# L-D5019-08.net
KiCad netlist of a schematic drawn in Altium Designer
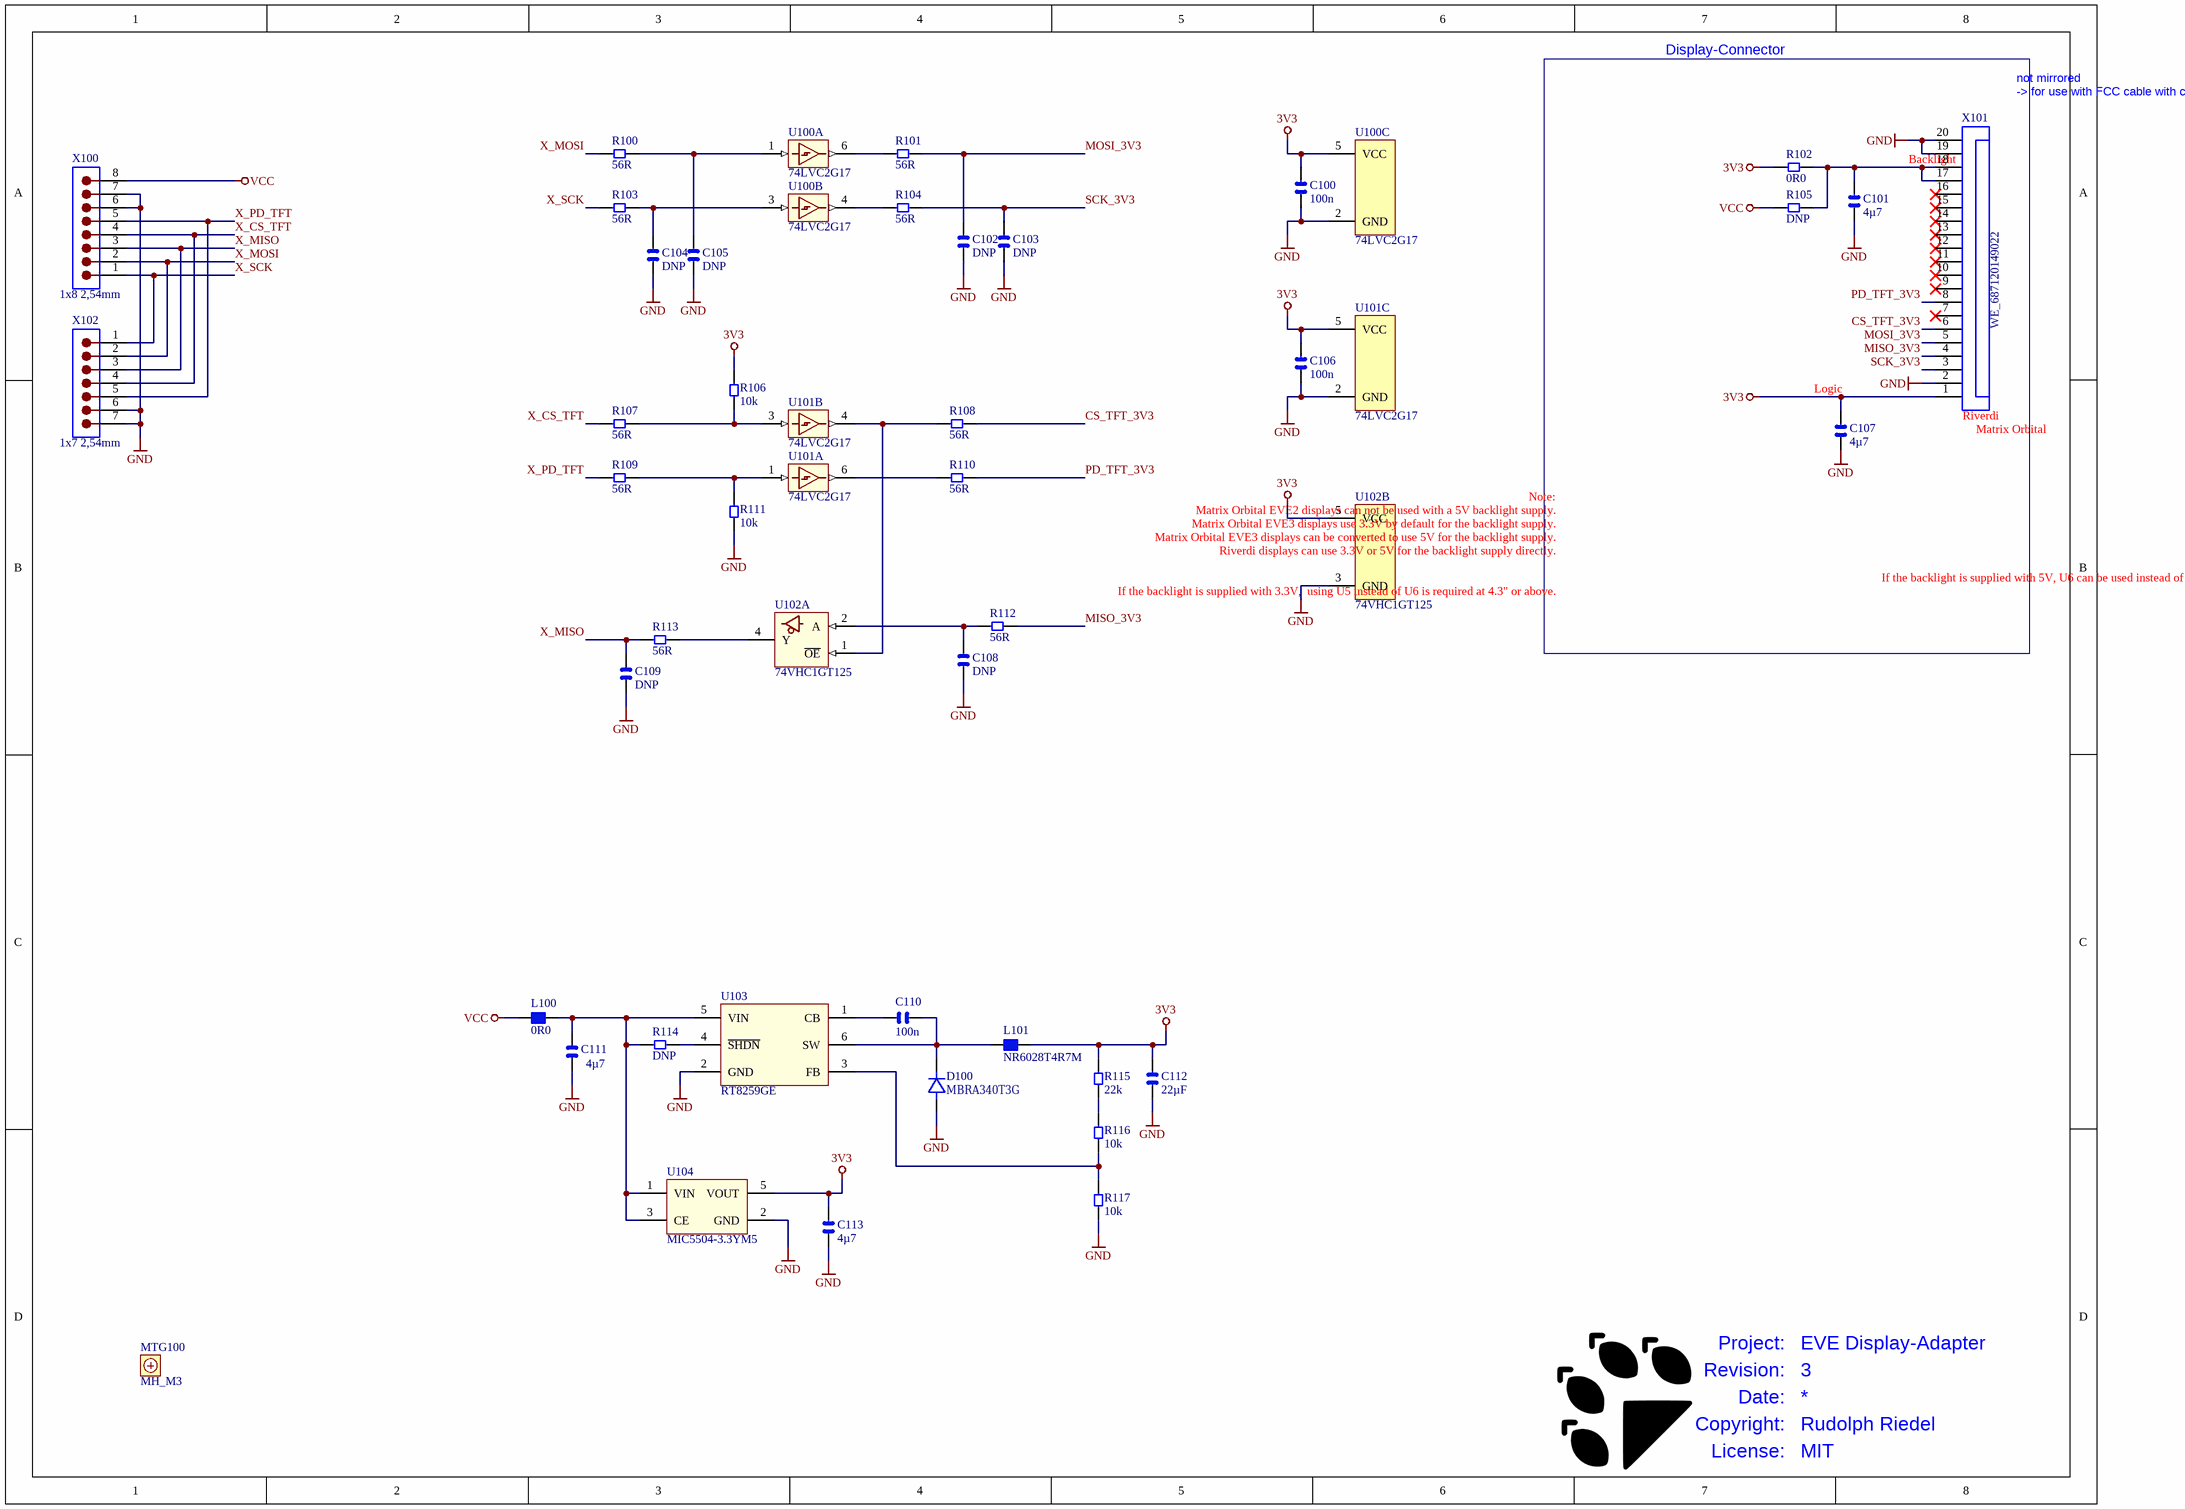
[diagram p0: L-D5019-08.SchDoc]

(export (version "E")
  (design (tool "Eeschema 10.0.6"))
  (components
    (comp (ref "C100")
      (value "100n")
      (footprint "CAPC2012X14L")
      (description "0805 Chip Capacitor")
      (fields (field (name "PART NUMBER") "CAPC_0805") (field (name "EDITOR") "rriedel"))
      (libsource (lib "HW-Labor_GF") (part "CAP_2_V2"))
    )
    (comp (ref "C101")
      (value "4µ7")
      (footprint "CAPC2012X14L")
      (description "0805 Chip Capacitor")
      (fields (field (name "PART NUMBER") "CAPC_0805") (field (name "ERSTELLER") "rriedel"))
      (libsource (lib "HW-Labor_GF") (part "CAP_2_V2"))
    )
    (comp (ref "C102")
      (value "DNP")
      (footprint "CAPC2012X14L")
      (description "0805 Chip Capacitor")
      (fields (field (name "PART NUMBER") "CAPC_0805") (field (name "EDITOR") "rriedel"))
      (libsource (lib "HW-Labor_GF") (part "CAP_2_V2"))
    )
    (comp (ref "C103")
      (value "DNP")
      (footprint "CAPC2012X14L")
      (description "0805 Chip Capacitor")
      (fields (field (name "PART NUMBER") "CAPC_0805") (field (name "EDITOR") "rriedel"))
      (libsource (lib "HW-Labor_GF") (part "CAP_2_V2"))
    )
    (comp (ref "C104")
      (value "DNP")
      (footprint "CAPC2012X14L")
      (description "0805 Chip Capacitor")
      (fields (field (name "PART NUMBER") "CAPC_0805") (field (name "EDITOR") "rriedel"))
      (libsource (lib "HW-Labor_GF") (part "CAP_2_V2"))
    )
    (comp (ref "C105")
      (value "DNP")
      (footprint "CAPC2012X14L")
      (description "0805 Chip Capacitor")
      (fields (field (name "PART NUMBER") "CAPC_0805") (field (name "EDITOR") "rriedel"))
      (libsource (lib "HW-Labor_GF") (part "CAP_2_V2"))
    )
    (comp (ref "C106")
      (value "100n")
      (footprint "CAPC2012X14L")
      (description "0805 Chip Capacitor")
      (fields (field (name "PART NUMBER") "CAPC_0805") (field (name "EDITOR") "rriedel"))
      (libsource (lib "HW-Labor_GF") (part "CAP_2_V2"))
    )
    (comp (ref "C107")
      (value "4µ7")
      (footprint "CAPC2012X14L")
      (description "0805 Chip Capacitor")
      (fields (field (name "PART NUMBER") "CAPC_0805") (field (name "ERSTELLER") "rriedel"))
      (libsource (lib "HW-Labor_GF") (part "CAP_2_V2"))
    )
    (comp (ref "C108")
      (value "DNP")
      (footprint "CAPC2012X14L")
      (description "0805 Chip Capacitor")
      (fields (field (name "PART NUMBER") "CAPC_0805") (field (name "EDITOR") "rriedel"))
      (libsource (lib "HW-Labor_GF") (part "CAP_2_V2"))
    )
    (comp (ref "C109")
      (value "DNP")
      (footprint "CAPC2012X14L")
      (description "0805 Chip Capacitor")
      (fields (field (name "PART NUMBER") "CAPC_0805") (field (name "EDITOR") "rriedel"))
      (libsource (lib "HW-Labor_GF") (part "CAP_2_V2"))
    )
    (comp (ref "C110")
      (value "100n")
      (footprint "CAPC2012X14L")
      (description "0805 Chip Capacitor")
      (fields (field (name "PART NUMBER") "CAPC_0805") (field (name "EDITOR") "rriedel"))
      (libsource (lib "HW-Labor_GF") (part "CAP_2_V2"))
    )
    (comp (ref "C111")
      (value "4µ7")
      (footprint "CAPC3216X19N")
      (description "1206 Chip Capacitor")
      (fields (field (name "PART NUMBER") "CAPC_1206") (field (name "EDITOR") "rriedel"))
      (libsource (lib "HW-Labor_GF") (part "CAP_2_V2"))
    )
    (comp (ref "C112")
      (value "22µF")
      (footprint "CAPC3216X19N")
      (description "1206 Chip Capacitor")
      (fields (field (name "PART NUMBER") "CAPC_1206") (field (name "EDITOR") "rriedel"))
      (libsource (lib "HW-Labor_GF") (part "CAP_2_V2"))
    )
    (comp (ref "C113")
      (value "4µ7")
      (footprint "CAPC2012X14L")
      (description "0805 Chip Capacitor")
      (fields (field (name "PART NUMBER") "CAPC_0805") (field (name "ERSTELLER") "rriedel"))
      (libsource (lib "HW-Labor_GF") (part "CAP_2_V2"))
    )
    (comp (ref "D100")
      (value "MBRA340T3G‎")
      (footprint "DIOM5226X23N")
      (description "Schottky Gleichrichterdiode, 40V / 3A / 450mV")
      (fields
        (field (name "MANUFACTURER") "ON Semiconductor")
        (field (name "DISTRIBUTOR_1_PART_NUMBER") "MBRA340T3GOSCT-ND")
        (field (name "EDITOR") "rriedel")
      )
      (libsource (lib "HW-Labor_GF") (part "Diode_A2_K1"))
    )
    (comp (ref "L100")
      (value "0R0")
      (footprint "INDC2012X10L")
      (description "0805 Chip Inductor")
      (fields (field (name "PART NUMBER") "INDC_0805") (field (name "EDITOR") "rriedel"))
      (libsource (lib "HW-Labor_GF") (part "IND_2_V1"))
    )
    (comp (ref "L101")
      (value "NR6028T4R7M")
      (footprint "TaiyoYuden_NR6028")
      (description "4,7µH, shielded, 2,7A, 40mR")
      (fields
        (field (name "MANUFACTURER") "Taiyo Yuden")
        (field (name "DISTRIBUTOR_1_PART_NUMBER") "587-2100-1-ND")
        (field (name "EDITOR") "rriedel")
      )
      (libsource (lib "HW-Labor_GF") (part "IND_2_V1"))
    )
    (comp (ref "MTG100")
      (value "MH_M3")
      (footprint "HOLE_3_2MM")
      (description "Mounting-Hole for M3 screws")
      (fields (field (name "EDITOR") "rriedel"))
      (libsource (lib "HW-Labor_GF") (part "MTG_V1"))
    )
    (comp (ref "R100")
      (value "56R")
      (footprint "RESC2012X06L")
      (description "0805 Chip Resistor")
      (fields (field (name "PART NUMBER") "RESC_0805") (field (name "EDITOR") "rriedel"))
      (libsource (lib "HW-Labor_GF") (part "RES_2_V2"))
    )
    (comp (ref "R101")
      (value "56R")
      (footprint "RESC2012X06L")
      (description "0805 Chip Resistor")
      (fields (field (name "PART NUMBER") "RESC_0805") (field (name "EDITOR") "rriedel"))
      (libsource (lib "HW-Labor_GF") (part "RES_2_V2"))
    )
    (comp (ref "R102")
      (value "0R0")
      (footprint "RESC2012X06L")
      (description "0805 Chip Resistor")
      (fields (field (name "PART NUMBER") "RESC_0805") (field (name "EDITOR") "rriedel"))
      (libsource (lib "HW-Labor_GF") (part "RES_2_V2"))
    )
    (comp (ref "R103")
      (value "56R")
      (footprint "RESC2012X06L")
      (description "0805 Chip Resistor")
      (fields (field (name "PART NUMBER") "RESC_0805") (field (name "EDITOR") "rriedel"))
      (libsource (lib "HW-Labor_GF") (part "RES_2_V2"))
    )
    (comp (ref "R104")
      (value "56R")
      (footprint "RESC2012X06L")
      (description "0805 Chip Resistor")
      (fields (field (name "PART NUMBER") "RESC_0805") (field (name "EDITOR") "rriedel"))
      (libsource (lib "HW-Labor_GF") (part "RES_2_V2"))
    )
    (comp (ref "R105")
      (value "DNP")
      (footprint "RESC2012X06L")
      (description "0805 Chip Resistor")
      (fields (field (name "PART NUMBER") "RESC_0805") (field (name "EDITOR") "rriedel"))
      (libsource (lib "HW-Labor_GF") (part "RES_2_V2"))
    )
    (comp (ref "R106")
      (value "10k")
      (footprint "RESC2012X06L")
      (description "0805 Chip Resistor")
      (fields (field (name "PART NUMBER") "RESC_0805") (field (name "EDITOR") "rriedel"))
      (libsource (lib "HW-Labor_GF") (part "RES_2_V2"))
    )
    (comp (ref "R107")
      (value "56R")
      (footprint "RESC2012X06L")
      (description "0805 Chip Resistor")
      (fields (field (name "PART NUMBER") "RESC_0805") (field (name "EDITOR") "rriedel"))
      (libsource (lib "HW-Labor_GF") (part "RES_2_V2"))
    )
    (comp (ref "R108")
      (value "56R")
      (footprint "RESC2012X06L")
      (description "0805 Chip Resistor")
      (fields (field (name "PART NUMBER") "RESC_0805") (field (name "EDITOR") "rriedel"))
      (libsource (lib "HW-Labor_GF") (part "RES_2_V2"))
    )
    (comp (ref "R109")
      (value "56R")
      (footprint "RESC2012X06L")
      (description "0805 Chip Resistor")
      (fields (field (name "PART NUMBER") "RESC_0805") (field (name "EDITOR") "rriedel"))
      (libsource (lib "HW-Labor_GF") (part "RES_2_V2"))
    )
    (comp (ref "R110")
      (value "56R")
      (footprint "RESC2012X06L")
      (description "0805 Chip Resistor")
      (fields (field (name "PART NUMBER") "RESC_0805") (field (name "EDITOR") "rriedel"))
      (libsource (lib "HW-Labor_GF") (part "RES_2_V2"))
    )
    (comp (ref "R111")
      (value "10k")
      (footprint "RESC2012X06L")
      (description "0805 Chip Resistor")
      (fields (field (name "PART NUMBER") "RESC_0805") (field (name "EDITOR") "rriedel"))
      (libsource (lib "HW-Labor_GF") (part "RES_2_V2"))
    )
    (comp (ref "R112")
      (value "56R")
      (footprint "RESC2012X06L")
      (description "0805 Chip Resistor")
      (fields (field (name "PART NUMBER") "RESC_0805") (field (name "EDITOR") "rriedel"))
      (libsource (lib "HW-Labor_GF") (part "RES_2_V2"))
    )
    (comp (ref "R113")
      (value "56R")
      (footprint "RESC2012X06L")
      (description "0805 Chip Resistor")
      (fields (field (name "PART NUMBER") "RESC_0805") (field (name "EDITOR") "rriedel"))
      (libsource (lib "HW-Labor_GF") (part "RES_2_V2"))
    )
    (comp (ref "R114")
      (value "DNP")
      (footprint "RESC2012X06L")
      (description "0805 Chip Resistor")
      (fields (field (name "PART NUMBER") "RESC_0805") (field (name "EDITOR") "rriedel"))
      (libsource (lib "HW-Labor_GF") (part "RES_2_V2"))
    )
    (comp (ref "R115")
      (value "22k")
      (footprint "RESC2012X06L")
      (description "0805 Chip Resistor")
      (fields (field (name "PART NUMBER") "RESC_0805") (field (name "EDITOR") "rriedel"))
      (libsource (lib "HW-Labor_GF") (part "RES_2_V2"))
    )
    (comp (ref "R116")
      (value "10k")
      (footprint "RESC2012X06L")
      (description "0805 Chip Resistor")
      (fields (field (name "PART NUMBER") "RESC_0805") (field (name "EDITOR") "rriedel"))
      (libsource (lib "HW-Labor_GF") (part "RES_2_V2"))
    )
    (comp (ref "R117")
      (value "10k")
      (footprint "RESC2012X06L")
      (description "0805 Chip Resistor")
      (fields (field (name "PART NUMBER") "RESC_0805") (field (name "EDITOR") "rriedel"))
      (libsource (lib "HW-Labor_GF") (part "RES_2_V2"))
    )
    (comp (ref "U100")
      (value "74LVC2G17")
      (footprint "SOT95P280X110-6N")
      (description "Dual Schmitt-Trigger Buffer with 5.5V tolerant inputs")
      (fields
        (field (name "MANUFACTURER") "TI")
        (field (name "DISTRIBUTOR_1_PART_NUMBER") "296-SN74LVC2G17DBVRCT-ND‎")
        (field (name "EDITOR") "rriedel")
      )
      (libsource (lib "HW-Labor_GF") (part "74LVC2G17"))
    )
    (comp (ref "U101")
      (value "74LVC2G17")
      (footprint "SOT95P280X110-6N")
      (description "Dual Schmitt-Trigger Buffer with 5.5V tolerant inputs")
      (fields
        (field (name "MANUFACTURER") "TI")
        (field (name "DISTRIBUTOR_1_PART_NUMBER") "296-SN74LVC2G17DBVRCT-ND‎")
        (field (name "EDITOR") "rriedel")
      )
      (libsource (lib "HW-Labor_GF") (part "74LVC2G17"))
    )
    (comp (ref "U102")
      (value "74VHC1GT125")
      (footprint "SOT95P280X110-5N")
      (description "1x Buffer with OE; 3-state,Level Shifter 3,3V to 5V and 5V to 3.3V")
      (fields
        (field (name "MANUFACTURER") "ON Semiconductor")
        (field (name "DISTRIBUTOR_1_PART_NUMBER") "1703291")
        (field (name "EDITOR") "rriedel")
      )
      (libsource (lib "HW-Labor_GF") (part "74LVC1G125G"))
    )
    (comp (ref "U103")
      (value "RT8259GE")
      (footprint "SOT95P280X110-6N")
      (description "Step-Down DC/DC Regulator, 24V, 1.2A, 1,4MHz")
      (fields
        (field (name "MANUFACTURER") "Richtek")
        (field (name "DISTRIBUTOR_1_PART_NUMBER") "1028-1497-1-ND")
        (field (name "EDITOR") "rriedel")
      )
      (libsource (lib "HW-Labor_GF") (part "StepDown_SOT23-6"))
    )
    (comp (ref "U104")
      (value "MIC5504-3.3YM5")
      (footprint "SOT95P280X110-5N")
      (description "300 mA LDO,  Vin=2,5V…5,5V, Vout= 3,3V, -40°C..125°C")
      (fields
        (field (name "MANUFACTURER") "Microchip")
        (field (name "DISTRIBUTOR_1_PART_NUMBER") "2510377")
        (field (name "EDITOR") "rriedel")
      )
      (libsource (lib "HW-Labor_GF") (part "LDO_SOT23-5"))
    )
    (comp (ref "X100")
      (value "1x8 2,54mm")
      (footprint "PINH_1x08_2_54mm")
      (description "Pin-Header 2,54 mm 8pins")
      (fields (field (name "PART NUMBER") "PINH_1x8_2_54") (field (name "EDITOR") "rriedel"))
      (libsource (lib "HW-Labor_GF") (part "CONM_1x8_V2"))
    )
    (comp (ref "X101")
      (value "WE_687120149022")
      (footprint "WE_687120149022")
      (description "20pin WR-FPC 0.50 mm SMT ZIF Horizontal - Bottom Contact")
      (fields
        (field (name "MANUFACTURER") "Wuerth")
        (field (name "DISTRIBUTOR_1_PART_NUMBER") "732-6002-1-ND")
        (field (name "EDITOR") "rriedel")
      )
      (libsource (lib "HW-Labor_GF") (part "FPC_20"))
    )
    (comp (ref "X102")
      (value "1x7 2,54mm")
      (footprint "PINH_1x07_2_54mm")
      (description "Pin-Header 2,54 mm 7pins")
      (fields (field (name "PART NUMBER") "PINH_1x7_2_54") (field (name "EDITOR") "rriedel"))
      (libsource (lib "HW-Labor_GF") (part "CONM_1x7_V2"))
    )
  )
  (nets
    (net (code "1") (name "/CS_TFT_3V3") (class "Default")
      (node (ref "R108") (pin "2") (pinfunction "2_2") (pintype "passive"))
      (node (ref "X101") (pin "6") (pinfunction "6_6") (pintype "passive"))
    )
    (net (code "2") (name "/MISO_3V3") (class "Default")
      (node (ref "R112") (pin "2") (pinfunction "2_2") (pintype "passive"))
      (node (ref "X101") (pin "4") (pinfunction "4_4") (pintype "passive"))
    )
    (net (code "3") (name "/MOSI_3V3") (class "Default")
      (node (ref "C102") (pin "2") (pinfunction "2_2") (pintype "passive"))
      (node (ref "R101") (pin "2") (pinfunction "2_2") (pintype "passive"))
      (node (ref "X101") (pin "5") (pinfunction "5_5") (pintype "passive"))
    )
    (net (code "4") (name "/PD_TFT_3V3") (class "Default")
      (node (ref "R110") (pin "2") (pinfunction "2_2") (pintype "passive"))
      (node (ref "X101") (pin "8") (pinfunction "8_8") (pintype "passive"))
    )
    (net (code "5") (name "/SCK_3V3") (class "Default")
      (node (ref "C103") (pin "2") (pinfunction "2_2") (pintype "passive"))
      (node (ref "R104") (pin "2") (pinfunction "2_2") (pintype "passive"))
      (node (ref "X101") (pin "3") (pinfunction "3_3") (pintype "passive"))
    )
    (net (code "6") (name "/X_CS_TFT") (class "Default")
      (node (ref "R107") (pin "1") (pinfunction "1_1") (pintype "passive"))
      (node (ref "X100") (pin "4") (pinfunction "4_4") (pintype "passive"))
      (node (ref "X102") (pin "4") (pinfunction "4_4") (pintype "passive"))
    )
    (net (code "7") (name "/X_MISO") (class "Default")
      (node (ref "C109") (pin "2") (pinfunction "2_2") (pintype "passive"))
      (node (ref "R113") (pin "1") (pinfunction "1_1") (pintype "passive"))
      (node (ref "X100") (pin "3") (pinfunction "3_3") (pintype "passive"))
      (node (ref "X102") (pin "3") (pinfunction "3_3") (pintype "passive"))
    )
    (net (code "8") (name "/X_MOSI") (class "Default")
      (node (ref "R100") (pin "1") (pinfunction "1_1") (pintype "passive"))
      (node (ref "X100") (pin "2") (pinfunction "2_2") (pintype "passive"))
      (node (ref "X102") (pin "2") (pinfunction "2_2") (pintype "passive"))
    )
    (net (code "9") (name "/X_PD_TFT") (class "Default")
      (node (ref "R109") (pin "1") (pinfunction "1_1") (pintype "passive"))
      (node (ref "X100") (pin "5") (pinfunction "5_5") (pintype "passive"))
      (node (ref "X102") (pin "5") (pinfunction "5_5") (pintype "passive"))
    )
    (net (code "10") (name "/X_SCK") (class "Default")
      (node (ref "R103") (pin "1") (pinfunction "1_1") (pintype "passive"))
      (node (ref "X100") (pin "1") (pinfunction "1_1") (pintype "passive"))
      (node (ref "X102") (pin "1") (pinfunction "1_1") (pintype "passive"))
    )
    (net (code "11") (name "3V3") (class "Default")
      (node (ref "C100") (pin "2") (pinfunction "2_2") (pintype "passive"))
      (node (ref "C106") (pin "2") (pinfunction "2_2") (pintype "passive"))
      (node (ref "C107") (pin "2") (pinfunction "2_2") (pintype "passive"))
      (node (ref "C112") (pin "2") (pinfunction "2_2") (pintype "passive"))
      (node (ref "C113") (pin "2") (pinfunction "2_2") (pintype "passive"))
      (node (ref "L101") (pin "2") (pinfunction "2_2") (pintype "passive"))
      (node (ref "R102") (pin "1") (pinfunction "1_1") (pintype "passive"))
      (node (ref "R106") (pin "2") (pinfunction "2_2") (pintype "passive"))
      (node (ref "R115") (pin "2") (pinfunction "2_2") (pintype "passive"))
      (node (ref "U100") (pin "5") (pinfunction "VCC_5") (pintype "power_in"))
      (node (ref "U101") (pin "5") (pinfunction "VCC_5") (pintype "power_in"))
      (node (ref "U102") (pin "5") (pinfunction "VCC_5") (pintype "passive"))
      (node (ref "U104") (pin "5") (pinfunction "VOUT_5") (pintype "passive"))
      (node (ref "X101") (pin "1") (pinfunction "1_1") (pintype "passive"))
    )
    (net (code "12") (name "GND") (class "Default")
      (node (ref "C100") (pin "1") (pinfunction "1_1") (pintype "passive"))
      (node (ref "C101") (pin "1") (pinfunction "1_1") (pintype "passive"))
      (node (ref "C102") (pin "1") (pinfunction "1_1") (pintype "passive"))
      (node (ref "C103") (pin "1") (pinfunction "1_1") (pintype "passive"))
      (node (ref "C104") (pin "1") (pinfunction "1_1") (pintype "passive"))
      (node (ref "C105") (pin "1") (pinfunction "1_1") (pintype "passive"))
      (node (ref "C106") (pin "1") (pinfunction "1_1") (pintype "passive"))
      (node (ref "C107") (pin "1") (pinfunction "1_1") (pintype "passive"))
      (node (ref "C108") (pin "1") (pinfunction "1_1") (pintype "passive"))
      (node (ref "C109") (pin "1") (pinfunction "1_1") (pintype "passive"))
      (node (ref "C111") (pin "1") (pinfunction "1_1") (pintype "passive"))
      (node (ref "C112") (pin "1") (pinfunction "1_1") (pintype "passive"))
      (node (ref "C113") (pin "1") (pinfunction "1_1") (pintype "passive"))
      (node (ref "D100") (pin "2") (pinfunction "2_2") (pintype "passive"))
      (node (ref "R111") (pin "1") (pinfunction "1_1") (pintype "passive"))
      (node (ref "R117") (pin "1") (pinfunction "1_1") (pintype "passive"))
      (node (ref "U100") (pin "2") (pinfunction "GND_2") (pintype "power_in"))
      (node (ref "U101") (pin "2") (pinfunction "GND_2") (pintype "power_in"))
      (node (ref "U102") (pin "3") (pinfunction "GND_3") (pintype "passive"))
      (node (ref "U103") (pin "2") (pinfunction "GND_2") (pintype "power_in"))
      (node (ref "U104") (pin "2") (pinfunction "GND_2") (pintype "passive"))
      (node (ref "X100") (pin "6") (pinfunction "6_6") (pintype "passive"))
      (node (ref "X100") (pin "7") (pinfunction "7_7") (pintype "passive"))
      (node (ref "X101") (pin "19") (pinfunction "19_19") (pintype "passive"))
      (node (ref "X101") (pin "2") (pinfunction "2_2") (pintype "passive"))
      (node (ref "X101") (pin "20") (pinfunction "20_20") (pintype "passive"))
      (node (ref "X102") (pin "6") (pinfunction "6_6") (pintype "passive"))
      (node (ref "X102") (pin "7") (pinfunction "7_7") (pintype "passive"))
    )
    (net (code "13") (name "Net-(C101-Pad2)") (class "Default")
      (node (ref "C101") (pin "2") (pinfunction "2_2") (pintype "passive"))
      (node (ref "R102") (pin "2") (pinfunction "2_2") (pintype "passive"))
      (node (ref "R105") (pin "2") (pinfunction "2_2") (pintype "passive"))
      (node (ref "X101") (pin "17") (pinfunction "17_17") (pintype "passive"))
      (node (ref "X101") (pin "18") (pinfunction "18_18") (pintype "passive"))
    )
    (net (code "14") (name "Net-(R115-Pad1)") (class "Default")
      (node (ref "R115") (pin "1") (pinfunction "1_1") (pintype "passive"))
      (node (ref "R116") (pin "2") (pinfunction "2_2") (pintype "passive"))
    )
    (net (code "15") (name "Net-(U100A-1A)") (class "Default")
      (node (ref "C105") (pin "2") (pinfunction "2_2") (pintype "passive"))
      (node (ref "R100") (pin "2") (pinfunction "2_2") (pintype "passive"))
      (node (ref "U100") (pin "1") (pinfunction "1A_1") (pintype "input"))
    )
    (net (code "16") (name "Net-(U100A-1Y)") (class "Default")
      (node (ref "R101") (pin "1") (pinfunction "1_1") (pintype "passive"))
      (node (ref "U100") (pin "6") (pinfunction "1Y_6") (pintype "output"))
    )
    (net (code "17") (name "Net-(U100B-2A)") (class "Default")
      (node (ref "C104") (pin "2") (pinfunction "2_2") (pintype "passive"))
      (node (ref "R103") (pin "2") (pinfunction "2_2") (pintype "passive"))
      (node (ref "U100") (pin "3") (pinfunction "2A_3") (pintype "input"))
    )
    (net (code "18") (name "Net-(U100B-2Y)") (class "Default")
      (node (ref "R104") (pin "1") (pinfunction "1_1") (pintype "passive"))
      (node (ref "U100") (pin "4") (pinfunction "2Y_4") (pintype "output"))
    )
    (net (code "19") (name "Net-(U101A-1A)") (class "Default")
      (node (ref "R109") (pin "2") (pinfunction "2_2") (pintype "passive"))
      (node (ref "R111") (pin "2") (pinfunction "2_2") (pintype "passive"))
      (node (ref "U101") (pin "1") (pinfunction "1A_1") (pintype "input"))
    )
    (net (code "20") (name "Net-(U101A-1Y)") (class "Default")
      (node (ref "R110") (pin "1") (pinfunction "1_1") (pintype "passive"))
      (node (ref "U101") (pin "6") (pinfunction "1Y_6") (pintype "output"))
    )
    (net (code "21") (name "Net-(U101B-2A)") (class "Default")
      (node (ref "R106") (pin "1") (pinfunction "1_1") (pintype "passive"))
      (node (ref "R107") (pin "2") (pinfunction "2_2") (pintype "passive"))
      (node (ref "U101") (pin "3") (pinfunction "2A_3") (pintype "input"))
    )
    (net (code "22") (name "Net-(U101B-2Y)") (class "Default")
      (node (ref "R108") (pin "1") (pinfunction "1_1") (pintype "passive"))
      (node (ref "U101") (pin "4") (pinfunction "2Y_4") (pintype "output"))
      (node (ref "U102") (pin "1") (pinfunction "~{OE}_1") (pintype "input"))
    )
    (net (code "23") (name "Net-(U102A-A)") (class "Default")
      (node (ref "C108") (pin "2") (pinfunction "2_2") (pintype "passive"))
      (node (ref "R112") (pin "1") (pinfunction "1_1") (pintype "passive"))
      (node (ref "U102") (pin "2") (pinfunction "A_2") (pintype "input"))
    )
    (net (code "24") (name "Net-(U102A-Y)") (class "Default")
      (node (ref "R113") (pin "2") (pinfunction "2_2") (pintype "passive"))
      (node (ref "U102") (pin "4") (pinfunction "Y_4") (pintype "tri_state"))
    )
    (net (code "25") (name "Net-(U103-CB)") (class "Default")
      (node (ref "C110") (pin "1") (pinfunction "1_1") (pintype "passive"))
      (node (ref "U103") (pin "1") (pinfunction "CB_1") (pintype "passive"))
    )
    (net (code "26") (name "Net-(U103-FB)") (class "Default")
      (node (ref "R116") (pin "1") (pinfunction "1_1") (pintype "passive"))
      (node (ref "R117") (pin "2") (pinfunction "2_2") (pintype "passive"))
      (node (ref "U103") (pin "3") (pinfunction "FB_3") (pintype "passive"))
    )
    (net (code "27") (name "Net-(U103-SW)") (class "Default")
      (node (ref "C110") (pin "2") (pinfunction "2_2") (pintype "passive"))
      (node (ref "D100") (pin "1") (pinfunction "1_1") (pintype "passive"))
      (node (ref "L101") (pin "1") (pinfunction "1_1") (pintype "passive"))
      (node (ref "U103") (pin "6") (pinfunction "SW_6") (pintype "passive"))
    )
    (net (code "28") (name "Net-(U103-VIN)") (class "Default")
      (node (ref "C111") (pin "2") (pinfunction "2_2") (pintype "passive"))
      (node (ref "L100") (pin "2") (pinfunction "2_2") (pintype "passive"))
      (node (ref "R114") (pin "1") (pinfunction "1_1") (pintype "passive"))
      (node (ref "U103") (pin "5") (pinfunction "VIN_5") (pintype "power_in"))
      (node (ref "U104") (pin "1") (pinfunction "VIN_1") (pintype "passive"))
      (node (ref "U104") (pin "3") (pinfunction "CE_3") (pintype "passive"))
    )
    (net (code "29") (name "Net-(U103-~{SHDN})") (class "Default")
      (node (ref "R114") (pin "2") (pinfunction "2_2") (pintype "passive"))
      (node (ref "U103") (pin "4") (pinfunction "~{SHDN}_4") (pintype "passive"))
    )
    (net (code "30") (name "VCC") (class "Default")
      (node (ref "L100") (pin "1") (pinfunction "1_1") (pintype "passive"))
      (node (ref "R105") (pin "1") (pinfunction "1_1") (pintype "passive"))
      (node (ref "X100") (pin "8") (pinfunction "8_8") (pintype "passive"))
    )
    (net (code "31") (name "unconnected-(X101-Pad7)") (class "Default")
      (node (ref "X101") (pin "7") (pinfunction "7_7") (pintype "passive+no_connect"))
    )
    (net (code "32") (name "unconnected-(X101-Pad9)") (class "Default")
      (node (ref "X101") (pin "9") (pinfunction "9_9") (pintype "passive+no_connect"))
    )
    (net (code "33") (name "unconnected-(X101-Pad10)") (class "Default")
      (node (ref "X101") (pin "10") (pinfunction "10_10") (pintype "passive+no_connect"))
    )
    (net (code "34") (name "unconnected-(X101-Pad11)") (class "Default")
      (node (ref "X101") (pin "11") (pinfunction "11_11") (pintype "passive+no_connect"))
    )
    (net (code "35") (name "unconnected-(X101-Pad12)") (class "Default")
      (node (ref "X101") (pin "12") (pinfunction "12_12") (pintype "passive+no_connect"))
    )
    (net (code "36") (name "unconnected-(X101-Pad13)") (class "Default")
      (node (ref "X101") (pin "13") (pinfunction "13_13") (pintype "passive+no_connect"))
    )
    (net (code "37") (name "unconnected-(X101-Pad14)") (class "Default")
      (node (ref "X101") (pin "14") (pinfunction "14_14") (pintype "passive+no_connect"))
    )
    (net (code "38") (name "unconnected-(X101-Pad15)") (class "Default")
      (node (ref "X101") (pin "15") (pinfunction "15_15") (pintype "passive+no_connect"))
    )
    (net (code "39") (name "unconnected-(X101-Pad16)") (class "Default")
      (node (ref "X101") (pin "16") (pinfunction "16_16") (pintype "passive+no_connect"))
    )
  )
)
